# CP125-_12V2A__V1_0.net
KiCad netlist of a schematic drawn in Altium Designer
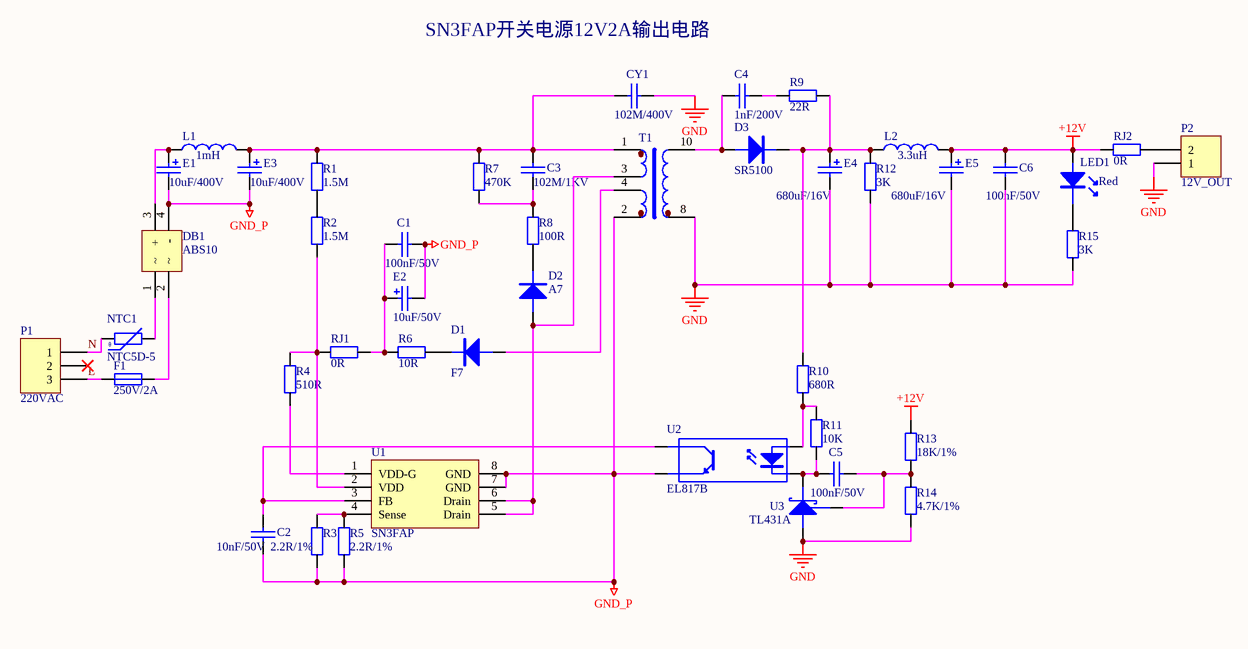
[diagram p0: CP125-(12V2A)_V1.0.SchDoc]

(export (version "E")
  (design (tool "Eeschema 10.0.6"))
  (components
    (comp (ref "C1")
      (value "100nF/50V")
      (footprint "Cheng_Resistor_Capacitor:0805_C1")
      (libsource (lib "Cheng_Resistor_Capacitor") (part "Cap1"))
    )
    (comp (ref "C2")
      (value "10nF/50V")
      (footprint "Cheng_Resistor_Capacitor:0805_C1")
      (libsource (lib "Cheng_Resistor_Capacitor") (part "Cap1"))
    )
    (comp (ref "C3")
      (value "102M/1KV")
      (footprint "Cheng_Resistor_Capacitor:CY-5MM")
      (libsource (lib "Cheng_Resistor_Capacitor") (part "Cap1"))
    )
    (comp (ref "C4")
      (value "1nF/200V")
      (footprint "Cheng_Resistor_Capacitor:0805_C1")
      (libsource (lib "Cheng_Resistor_Capacitor") (part "Cap1"))
    )
    (comp (ref "C5")
      (value "100nF/50V")
      (footprint "Cheng_Resistor_Capacitor:0603_CN")
      (libsource (lib "Cheng_Resistor_Capacitor") (part "Cap1"))
    )
    (comp (ref "C6")
      (value "100nF/50V")
      (footprint "Cheng_Resistor_Capacitor:0805_C1")
      (libsource (lib "Cheng_Resistor_Capacitor") (part "Cap1"))
    )
    (comp (ref "CY1")
      (value "102M/400V")
      (footprint "Cheng_Resistor_Capacitor:CY-10MM")
      (libsource (lib "Cheng_Resistor_Capacitor") (part "Cap Y"))
    )
    (comp (ref "D1")
      (value "F7")
      (footprint "Cheng_Diode_Transistor:SOD-123")
      (description "SS14,SS24,SS34,M7")
      (libsource (lib "Cheng_Diode_Transistor") (part "Diode-A"))
    )
    (comp (ref "D2")
      (value "A7")
      (footprint "Cheng_Diode_Transistor:SOD-123")
      (description "SS14,SS24,SS34,M7")
      (libsource (lib "Cheng_Diode_Transistor") (part "Diode-A"))
    )
    (comp (ref "D3")
      (value "SR5100")
      (footprint "Cheng_Diode_Transistor:DO-201AD-1")
      (description "SS14,SS24,SS34,M7")
      (libsource (lib "Cheng_Diode_Transistor") (part "Diode-A"))
    )
    (comp (ref "DB1")
      (value "ABS10")
      (footprint "Cheng_Diode_Transistor:ABS10")
      (description "0.8A/1000V")
      (libsource (lib "Cheng_Diode_Transistor") (part "ABS10"))
    )
    (comp (ref "E1")
      (value "10uF/400V")
      (footprint "Cheng_Resistor_Capacitor:CS_470uF/16V")
      (libsource (lib "Cheng_Resistor_Capacitor") (part "Cap Pol1"))
    )
    (comp (ref "E2")
      (value "10uF/50V")
      (footprint "Cheng_Resistor_Capacitor:CS_47uF/25V")
      (libsource (lib "Cheng_Resistor_Capacitor") (part "Cap Pol1"))
    )
    (comp (ref "E3")
      (value "10uF/400V")
      (footprint "Cheng_Resistor_Capacitor:CS_470uF/16V")
      (libsource (lib "Cheng_Resistor_Capacitor") (part "Cap Pol1"))
    )
    (comp (ref "E4")
      (value "680uF/16V")
      (footprint "Cheng_Resistor_Capacitor:CS_220uF/25V")
      (libsource (lib "Cheng_Resistor_Capacitor") (part "Cap Pol1"))
    )
    (comp (ref "E5")
      (value "680uF/16V")
      (footprint "Cheng_Resistor_Capacitor:CS_220uF/25V")
      (libsource (lib "Cheng_Resistor_Capacitor") (part "Cap Pol1"))
    )
    (comp (ref "F1")
      (value "250V/2A")
      (footprint "Cheng_Manostat:FUSE3*10MM-A")
      (description "Fuse")
      (libsource (lib "Cheng_Manostat") (part "FUSE1"))
    )
    (comp (ref "L1")
      (value "1mH")
      (footprint "Cheng_Resistor_Capacitor:Inductance-8*10")
      (libsource (lib "Cheng_Resistor_Capacitor") (part "Inductor"))
    )
    (comp (ref "L2")
      (value "3.3uH")
      (footprint "Cheng_Resistor_Capacitor:Inductance-8*10")
      (libsource (lib "Cheng_Resistor_Capacitor") (part "Inductor"))
    )
    (comp (ref "LED1")
      (value "Red")
      (footprint "Cheng_Diode_Transistor:3MM_LED")
      (libsource (lib "Cheng_Diode_Transistor") (part "LED"))
    )
    (comp (ref "NTC1")
      (value "NTC5D-5")
      (footprint "Cheng_Resistor_Capacitor:NTC5D-5")
      (libsource (lib "Cheng_Resistor_Capacitor") (part "Res NTC"))
    )
    (comp (ref "P1")
      (value "220VAC")
      (footprint "Cheng_Interface Unit:KF5.08-3P")
      (description "Header, 3-Pin")
      (fields (field (name "PUBLISHER") "Altium Limited"))
      (libsource (lib "Cheng_Interface Unit") (part "Header 3"))
    )
    (comp (ref "P2")
      (value "12V_OUT")
      (footprint "Cheng_Interface Unit:KF5.08-2P")
      (description "Header, 2-Pin")
      (fields (field (name "PUBLISHER") "Altium Limited"))
      (libsource (lib "Cheng_Interface Unit") (part "Header 2"))
    )
    (comp (ref "R1")
      (value "1.5M")
      (footprint "Cheng_Resistor_Capacitor:1206_R")
      (libsource (lib "") (part "Res1_2"))
    )
    (comp (ref "R2")
      (value "1.5M")
      (footprint "Cheng_Resistor_Capacitor:1206_R")
      (libsource (lib "") (part "Res1_2"))
    )
    (comp (ref "R3")
      (value "2.2R/1%")
      (footprint "Cheng_Resistor_Capacitor:1206_R")
      (libsource (lib "") (part "Res1_2"))
    )
    (comp (ref "R4")
      (value "510R")
      (footprint "Cheng_Resistor_Capacitor:0805_R")
      (libsource (lib "") (part "Res1_2"))
    )
    (comp (ref "R5")
      (value "2.2R/1%")
      (footprint "Cheng_Resistor_Capacitor:1206_R")
      (libsource (lib "") (part "Res1_2"))
    )
    (comp (ref "R6")
      (value "10R")
      (footprint "Cheng_Resistor_Capacitor:0805_R")
      (libsource (lib "") (part "Res1_3"))
    )
    (comp (ref "R7")
      (value "470K")
      (footprint "Cheng_Resistor_Capacitor:1206_R")
      (libsource (lib "") (part "Res1_2"))
    )
    (comp (ref "R8")
      (value "100R")
      (footprint "Cheng_Resistor_Capacitor:1206_R")
      (libsource (lib "") (part "Res1_2"))
    )
    (comp (ref "R9")
      (value "22R")
      (footprint "Cheng_Resistor_Capacitor:1206_R")
      (libsource (lib "") (part "Res1_3"))
    )
    (comp (ref "R10")
      (value "680R")
      (footprint "Cheng_Resistor_Capacitor:0603_RN")
      (libsource (lib "") (part "Res1_1"))
    )
    (comp (ref "R11")
      (value "10K")
      (footprint "Cheng_Resistor_Capacitor:0603_RN")
      (libsource (lib "") (part "Res1_1"))
    )
    (comp (ref "R12")
      (value "3K")
      (footprint "Cheng_Resistor_Capacitor:1206_R")
      (libsource (lib "") (part "Res1_2"))
    )
    (comp (ref "R13")
      (value "18K/1%")
      (footprint "Cheng_Resistor_Capacitor:0603_RN")
      (libsource (lib "") (part "Res1_2"))
    )
    (comp (ref "R14")
      (value "4.7K/1%")
      (footprint "Cheng_Resistor_Capacitor:0603_RN")
      (libsource (lib "") (part "Res1_2"))
    )
    (comp (ref "R15")
      (value "3K")
      (footprint "Cheng_Resistor_Capacitor:0805_R")
      (libsource (lib "") (part "Res1_2"))
    )
    (comp (ref "RJ1")
      (value "0R")
      (footprint "Cheng_Resistor_Capacitor:0805_R")
      (libsource (lib "Cheng_Resistor_Capacitor") (part "Res1"))
    )
    (comp (ref "RJ2")
      (value "0R")
      (footprint "Cheng_Resistor_Capacitor:1206_R")
      (libsource (lib "Cheng_Resistor_Capacitor") (part "Res1"))
    )
    (comp (ref "T1")
      (value "EF20")
      (footprint "Cheng_Misc Component:EF20-H-5+5")
      (libsource (lib "CP125-(12V2A)_V1.0") (part "EF20"))
    )
    (comp (ref "U1")
      (value "SN3FAP")
      (footprint "Cheng_IC:DIP-8")
      (libsource (lib "Cheng_Manostat") (part "SN3FAP"))
    )
    (comp (ref "U2")
      (value "EL817B")
      (footprint "Cheng_IC:DIP-4")
      (libsource (lib "Cheng_Diode_Transistor") (part "PC817"))
    )
    (comp (ref "U3")
      (value "TL431A")
      (footprint "Cheng_Diode_Transistor:TO-92B")
      (libsource (lib "Cheng_Manostat") (part "TL431"))
    )
  )
  (nets
    (net (code "1") (name "+12V") (class "Default")
      (node (ref "C6") (pin "2") (pinfunction "2_2") (pintype "passive"))
      (node (ref "E5") (pin "1") (pinfunction "1_1") (pintype "passive"))
      (node (ref "L2") (pin "2") (pinfunction "2_2") (pintype "passive"))
      (node (ref "LED1") (pin "A") (pinfunction "1_A") (pintype "passive"))
      (node (ref "R13") (pin "2") (pinfunction "2_2") (pintype "passive"))
      (node (ref "RJ2") (pin "2") (pinfunction "2_2") (pintype "passive"))
    )
    (net (code "2") (name "/L") (class "Default")
      (node (ref "F1") (pin "1") (pinfunction "1_1") (pintype "passive"))
      (node (ref "P1") (pin "3") (pinfunction "3_3") (pintype "passive"))
    )
    (net (code "3") (name "/N") (class "Default")
      (node (ref "NTC1") (pin "1") (pinfunction "1_1") (pintype "passive"))
      (node (ref "P1") (pin "1") (pinfunction "1_1") (pintype "passive"))
    )
    (net (code "4") (name "GND") (class "Default")
      (node (ref "C6") (pin "1") (pinfunction "1_1") (pintype "passive"))
      (node (ref "CY1") (pin "2") (pinfunction "2_2") (pintype "passive"))
      (node (ref "E4") (pin "2") (pinfunction "2_2") (pintype "passive"))
      (node (ref "E5") (pin "2") (pinfunction "2_2") (pintype "passive"))
      (node (ref "P2") (pin "1") (pinfunction "1_1") (pintype "passive"))
      (node (ref "R12") (pin "1") (pinfunction "1_1") (pintype "passive"))
      (node (ref "R14") (pin "1") (pinfunction "1_1") (pintype "passive"))
      (node (ref "R15") (pin "1") (pinfunction "1_1") (pintype "passive"))
      (node (ref "T1") (pin "8") (pinfunction "8_8") (pintype "passive"))
      (node (ref "U3") (pin "2") (pinfunction "A_2") (pintype "passive"))
    )
    (net (code "5") (name "GND_P") (class "Default")
      (node (ref "C1") (pin "1") (pinfunction "1_1") (pintype "passive"))
      (node (ref "C2") (pin "2") (pinfunction "2_2") (pintype "passive"))
      (node (ref "DB1") (pin "4") (pinfunction "-_4") (pintype "passive"))
      (node (ref "E1") (pin "2") (pinfunction "2_2") (pintype "passive"))
      (node (ref "E2") (pin "2") (pinfunction "2_2") (pintype "passive"))
      (node (ref "E3") (pin "2") (pinfunction "2_2") (pintype "passive"))
      (node (ref "R3") (pin "1") (pinfunction "1_1") (pintype "passive"))
      (node (ref "R5") (pin "1") (pinfunction "1_1") (pintype "passive"))
      (node (ref "T1") (pin "2") (pinfunction "2_2") (pintype "passive"))
      (node (ref "U1") (pin "7") (pinfunction "GND_7") (pintype "passive"))
      (node (ref "U1") (pin "8") (pinfunction "GND_8") (pintype "passive"))
      (node (ref "U2") (pin "3") (pinfunction "E_3") (pintype "passive"))
    )
    (net (code "6") (name "Net-(C1-Pad2)") (class "Default")
      (node (ref "C1") (pin "2") (pinfunction "2_2") (pintype "passive"))
      (node (ref "E2") (pin "1") (pinfunction "1_1") (pintype "passive"))
      (node (ref "R6") (pin "1") (pinfunction "1_1") (pintype "passive"))
      (node (ref "RJ1") (pin "1") (pinfunction "1_1") (pintype "passive"))
    )
    (net (code "7") (name "Net-(C3-Pad1)") (class "Default")
      (node (ref "C3") (pin "1") (pinfunction "1_1") (pintype "passive"))
      (node (ref "CY1") (pin "1") (pinfunction "1_1") (pintype "passive"))
      (node (ref "E3") (pin "1") (pinfunction "1_1") (pintype "passive"))
      (node (ref "L1") (pin "2") (pinfunction "2_2") (pintype "passive"))
      (node (ref "R1") (pin "2") (pinfunction "2_2") (pintype "passive"))
      (node (ref "R7") (pin "2") (pinfunction "2_2") (pintype "passive"))
      (node (ref "T1") (pin "1") (pinfunction "1_1") (pintype "passive"))
    )
    (net (code "8") (name "Net-(C3-Pad2)") (class "Default")
      (node (ref "C3") (pin "2") (pinfunction "2_2") (pintype "passive"))
      (node (ref "R7") (pin "1") (pinfunction "1_1") (pintype "passive"))
      (node (ref "R8") (pin "2") (pinfunction "2_2") (pintype "passive"))
    )
    (net (code "9") (name "Net-(C4-Pad2)") (class "Default")
      (node (ref "C4") (pin "2") (pinfunction "2_2") (pintype "passive"))
      (node (ref "R9") (pin "1") (pinfunction "1_1") (pintype "passive"))
    )
    (net (code "10") (name "Net-(D1-1)") (class "Default")
      (node (ref "D1") (pin "A") (pinfunction "1_A") (pintype "passive"))
      (node (ref "T1") (pin "4") (pinfunction "4_4") (pintype "passive"))
    )
    (net (code "11") (name "Net-(D1-2)") (class "Default")
      (node (ref "D1") (pin "K") (pinfunction "2_K") (pintype "passive"))
      (node (ref "R6") (pin "2") (pinfunction "2_2") (pintype "passive"))
    )
    (net (code "12") (name "Net-(D2-1)") (class "Default")
      (node (ref "D2") (pin "A") (pinfunction "1_A") (pintype "passive"))
      (node (ref "T1") (pin "3") (pinfunction "3_3") (pintype "passive"))
      (node (ref "U1") (pin "5") (pinfunction "Drain_5") (pintype "passive"))
      (node (ref "U1") (pin "6") (pinfunction "Drain_6") (pintype "passive"))
    )
    (net (code "13") (name "Net-(D2-2)") (class "Default")
      (node (ref "D2") (pin "K") (pinfunction "2_K") (pintype "passive"))
      (node (ref "R8") (pin "1") (pinfunction "1_1") (pintype "passive"))
    )
    (net (code "14") (name "Net-(D3-1)") (class "Default")
      (node (ref "C4") (pin "1") (pinfunction "1_1") (pintype "passive"))
      (node (ref "D3") (pin "A") (pinfunction "1_A") (pintype "passive"))
      (node (ref "T1") (pin "10") (pinfunction "10_10") (pintype "passive"))
    )
    (net (code "15") (name "Net-(D3-2)") (class "Default")
      (node (ref "D3") (pin "K") (pinfunction "2_K") (pintype "passive"))
      (node (ref "E4") (pin "1") (pinfunction "1_1") (pintype "passive"))
      (node (ref "L2") (pin "1") (pinfunction "1_1") (pintype "passive"))
      (node (ref "R10") (pin "1") (pinfunction "1_1") (pintype "passive"))
      (node (ref "R12") (pin "2") (pinfunction "2_2") (pintype "passive"))
      (node (ref "R9") (pin "2") (pinfunction "2_2") (pintype "passive"))
    )
    (net (code "16") (name "Net-(DB1-+)") (class "Default")
      (node (ref "DB1") (pin "3") (pinfunction "+_3") (pintype "passive"))
      (node (ref "E1") (pin "1") (pinfunction "1_1") (pintype "passive"))
      (node (ref "L1") (pin "1") (pinfunction "1_1") (pintype "passive"))
    )
    (net (code "17") (name "Net-(DB1-~-Pad1)") (class "Default")
      (node (ref "DB1") (pin "1") (pinfunction "~_1") (pintype "passive"))
      (node (ref "NTC1") (pin "2") (pinfunction "2_2") (pintype "passive"))
    )
    (net (code "18") (name "Net-(DB1-~-Pad2)") (class "Default")
      (node (ref "DB1") (pin "2") (pinfunction "~_2") (pintype "passive"))
      (node (ref "F1") (pin "2") (pinfunction "2_2") (pintype "passive"))
    )
    (net (code "19") (name "Net-(LED1-2)") (class "Default")
      (node (ref "LED1") (pin "K") (pinfunction "2_K") (pintype "passive"))
      (node (ref "R15") (pin "2") (pinfunction "2_2") (pintype "passive"))
    )
    (net (code "20") (name "Net-(P2-Pad2)") (class "Default")
      (node (ref "P2") (pin "2") (pinfunction "2_2") (pintype "passive"))
      (node (ref "RJ2") (pin "1") (pinfunction "1_1") (pintype "passive"))
    )
    (net (code "21") (name "Net-(R1-Pad1)") (class "Default")
      (node (ref "R1") (pin "1") (pinfunction "1_1") (pintype "passive"))
      (node (ref "R2") (pin "2") (pinfunction "2_2") (pintype "passive"))
    )
    (net (code "22") (name "Net-(U1-FB)") (class "Default")
      (node (ref "C2") (pin "1") (pinfunction "1_1") (pintype "passive"))
      (node (ref "U1") (pin "3") (pinfunction "FB_3") (pintype "passive"))
      (node (ref "U2") (pin "4") (pinfunction "C_4") (pintype "passive"))
    )
    (net (code "23") (name "Net-(U1-Sense)") (class "Default")
      (node (ref "R3") (pin "2") (pinfunction "2_2") (pintype "passive"))
      (node (ref "R5") (pin "2") (pinfunction "2_2") (pintype "passive"))
      (node (ref "U1") (pin "4") (pinfunction "Sense_4") (pintype "passive"))
    )
    (net (code "24") (name "Net-(U1-VDD)") (class "Default")
      (node (ref "R2") (pin "1") (pinfunction "1_1") (pintype "passive"))
      (node (ref "R4") (pin "2") (pinfunction "2_2") (pintype "passive"))
      (node (ref "RJ1") (pin "2") (pinfunction "2_2") (pintype "passive"))
      (node (ref "U1") (pin "2") (pinfunction "VDD_2") (pintype "passive"))
    )
    (net (code "25") (name "Net-(U1-VDD-G)") (class "Default")
      (node (ref "R4") (pin "1") (pinfunction "1_1") (pintype "passive"))
      (node (ref "U1") (pin "1") (pinfunction "VDD-G_1") (pintype "passive"))
    )
    (net (code "26") (name "Net-(U2-A)") (class "Default")
      (node (ref "R10") (pin "2") (pinfunction "2_2") (pintype "passive"))
      (node (ref "R11") (pin "1") (pinfunction "1_1") (pintype "passive"))
      (node (ref "U2") (pin "1") (pinfunction "A_1") (pintype "passive"))
    )
    (net (code "27") (name "Net-(U2-K)") (class "Default")
      (node (ref "C5") (pin "1") (pinfunction "1_1") (pintype "passive"))
      (node (ref "R11") (pin "2") (pinfunction "2_2") (pintype "passive"))
      (node (ref "U2") (pin "2") (pinfunction "K_2") (pintype "passive"))
      (node (ref "U3") (pin "3") (pinfunction "K_3") (pintype "passive"))
    )
    (net (code "28") (name "Net-(U3-R)") (class "Default")
      (node (ref "C5") (pin "2") (pinfunction "2_2") (pintype "passive"))
      (node (ref "R13") (pin "1") (pinfunction "1_1") (pintype "passive"))
      (node (ref "R14") (pin "2") (pinfunction "2_2") (pintype "passive"))
      (node (ref "U3") (pin "1") (pinfunction "R_1") (pintype "passive"))
    )
    (net (code "29") (name "unconnected-(P1-Pad2)") (class "Default")
      (node (ref "P1") (pin "2") (pinfunction "2_2") (pintype "passive+no_connect"))
    )
  )
)
